# Solid-State_Sidekick_v1.net
KiCad netlist of a schematic drawn in EAGLE
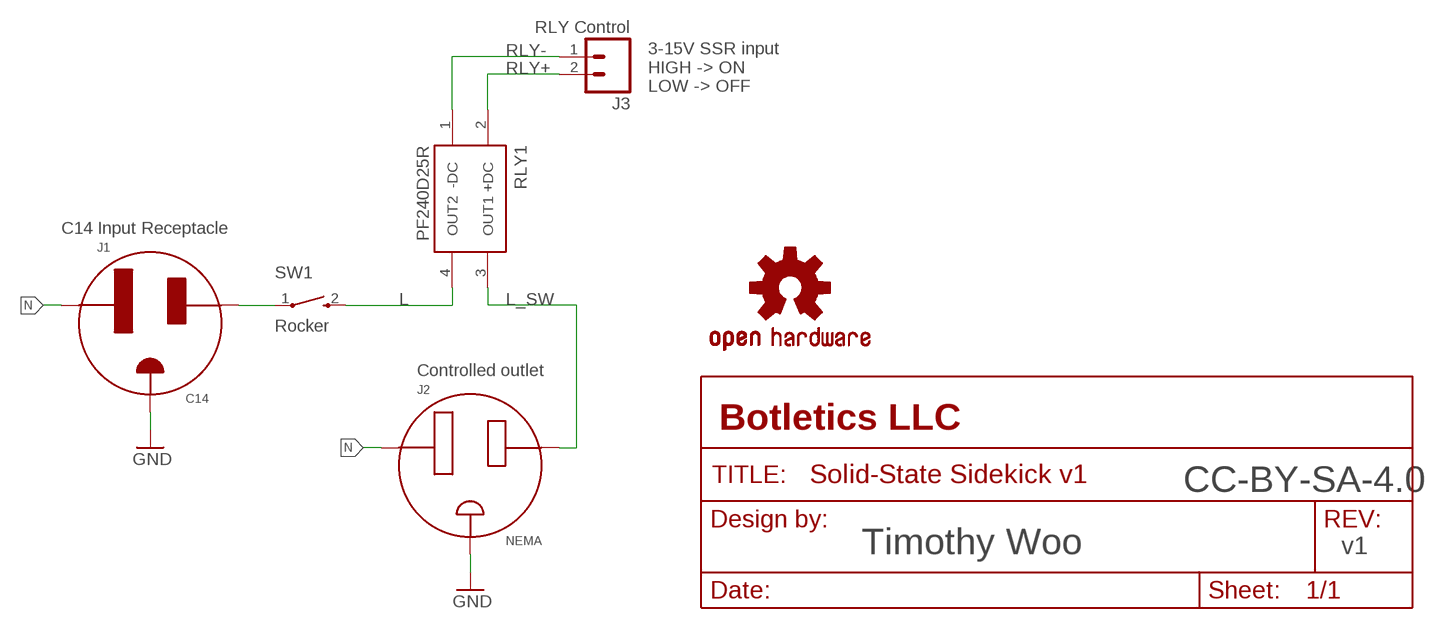
[diagram p0: schematic, sheet 1]

(export (version "E")
  (design (tool "Eeschema 10.0.6"))
  (components
    (comp (ref "J1")
      (value "C14")
      (footprint "eagle-import:703W-00_53")
      (libsource (lib "eagle-import") (part "AC_MALE_RECEPTACLEC14_RIGHTANGLE"))
    )
    (comp (ref "J2")
      (value "NEMA")
      (footprint "eagle-import:3-213598-2")
      (libsource (lib "eagle-import") (part "AC_FEMALE_RECEPTACLENEMA_5-15R"))
    )
    (comp (ref "J3")
      (value "RLY Control")
      (footprint "eagle-import:SCREWTERMINAL-3.5MM-2")
      (libsource (lib "eagle-import") (part "M023.5MM"))
    )
    (comp (ref "LOGO1")
      (value "OSHW-LOGOL")
      (footprint "eagle-import:OSHW-LOGO-L")
      (libsource (lib "eagle-import") (part "OSHW-LOGOL"))
    )
    (comp (ref "RLY1")
      (value "PF240D25R")
      (footprint "eagle-import:RELAY_PF240")
      (libsource (lib "eagle-import") (part "RELAY_SSR_OPTO-ISOLATEDPF240"))
    )
    (comp (ref "SW1")
      (value "Rocker")
      (footprint "eagle-import:R1966ABLKBLKFR")
      (libsource (lib "eagle-import") (part "SWITCH_SPST_2-PINROCKER"))
    )
  )
  (nets
    (net (code "1") (name "/L") (class "Default")
      (node (ref "RLY1") (pin "4") (pinfunction "OUT2_4") (pintype "bidirectional"))
      (node (ref "SW1") (pin "2") (pinfunction "2_2") (pintype "passive"))
    )
    (net (code "2") (name "/L_SW") (class "Default")
      (node (ref "J2") (pin "L") (pinfunction "L_L") (pintype "bidirectional"))
      (node (ref "RLY1") (pin "3") (pinfunction "OUT1_3") (pintype "bidirectional"))
    )
    (net (code "3") (name "/RLY+") (class "Default")
      (node (ref "J3") (pin "2") (pinfunction "2_2") (pintype "passive"))
      (node (ref "RLY1") (pin "2") (pinfunction "+DC_2") (pintype "bidirectional"))
    )
    (net (code "4") (name "/RLY-") (class "Default")
      (node (ref "J3") (pin "1") (pinfunction "1_1") (pintype "passive"))
      (node (ref "RLY1") (pin "1") (pinfunction "-DC_1") (pintype "bidirectional"))
    )
    (net (code "5") (name "GND") (class "Default")
      (node (ref "J1") (pin "E") (pinfunction "E_E") (pintype "bidirectional"))
      (node (ref "J2") (pin "GND") (pinfunction "E_GND") (pintype "bidirectional"))
    )
    (net (code "6") (name "N") (class "Default")
      (node (ref "J1") (pin "N") (pinfunction "N_N") (pintype "bidirectional"))
      (node (ref "J2") (pin "N") (pinfunction "N_N") (pintype "bidirectional"))
    )
    (net (code "7") (name "Net-(J1-PadL)") (class "Default")
      (node (ref "J1") (pin "L") (pinfunction "L_L") (pintype "bidirectional"))
      (node (ref "SW1") (pin "1") (pinfunction "1_1") (pintype "passive"))
    )
  )
)
